# BatteryChargerSwitch.net
KiCad netlist of a schematic drawn in Altium Designer
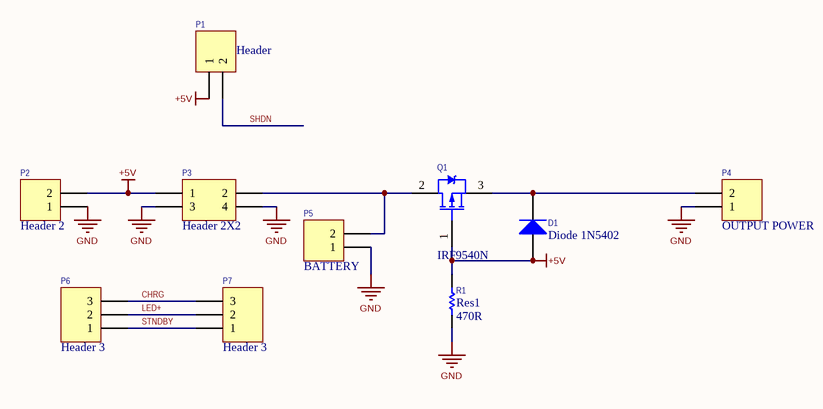
[diagram p0: BatteryChargerSwitch.SchDoc]

(export (version "E")
  (design (tool "Eeschema 10.0.6"))
  (components
    (comp (ref "D1")
      (value "Diode 1N5402")
      (footprint "1N5408 DO-201AD")
      (description "3 Amp General Purpose Rectifier")
      (fields (field (name "PUBLISHER") "Altium Limited"))
      (libsource (lib "Miscellaneous Devices") (part "Diode 1N5402"))
    )
    (comp (ref "P1")
      (value "Header")
      (footprint "KF301 2PIN")
      (description "Header, 2-Pin")
      (fields (field (name "PUBLISHER") "Altium Limited"))
      (libsource (lib "") (part "Header 2_1"))
    )
    (comp (ref "P2")
      (value "Header 2")
      (footprint "KF301 2PIN")
      (description "Header, 2-Pin")
      (fields (field (name "PUBLISHER") "Altium Limited"))
      (libsource (lib "Miscellaneous Connectors") (part "Header 2"))
    )
    (comp (ref "P3")
      (value "Header 2X2")
      (footprint "TP5100_MODULE")
      (description "Header, 2-Pin, Dual row")
      (fields (field (name "PUBLISHER") "Altium Limited"))
      (libsource (lib "Miscellaneous Connectors") (part "Header 2X2"))
    )
    (comp (ref "P4")
      (value "OUTPUT POWER")
      (footprint "KF301 2PIN")
      (description "Header, 2-Pin")
      (fields (field (name "PUBLISHER") "Altium Limited"))
      (libsource (lib "") (part "Header 2_1"))
    )
    (comp (ref "P5")
      (value "BATTERY")
      (footprint "KF301 2PIN")
      (description "Header, 2-Pin")
      (fields (field (name "PUBLISHER") "Altium Limited"))
      (libsource (lib "Miscellaneous Connectors") (part "Header 2"))
    )
    (comp (ref "P6")
      (value "Header 3")
      (footprint "HDR1X3")
      (description "Header, 3-Pin")
      (fields (field (name "PUBLISHER") "Altium Limited"))
      (libsource (lib "Miscellaneous Connectors") (part "Header 3"))
    )
    (comp (ref "P7")
      (value "Header 3")
      (footprint "HDR1X3")
      (description "Header, 3-Pin")
      (fields (field (name "PUBLISHER") "Altium Limited"))
      (libsource (lib "") (part "Header 3_1"))
    )
    (comp (ref "Q1")
      (value "IRF9540N")
      (footprint "TO-220 AB")
      (description "HEXFET Power MOSFET")
      (fields (field (name "PUBLISHER") "Altium Limited"))
      (libsource (lib "IR Discrete MOSFET - Power") (part "IRF9540N"))
    )
    (comp (ref "R1")
      (value "Res1")
      (footprint "Axial 0_25 W, 0_4 IN LEAD PITCH")
      (description "Resistor")
      (fields (field (name "ALTIUM_VALUE") "470R") (field (name "PUBLISHER") "Altium Limited"))
      (libsource (lib "Miscellaneous Devices") (part "Res1"))
    )
  )
  (nets
    (net (code "1") (name "+5V") (class "Default")
      (node (ref "D1") (pin "1") (pinfunction "A_1") (pintype "passive"))
      (node (ref "P1") (pin "1") (pinfunction "1_1") (pintype "passive"))
      (node (ref "P2") (pin "2") (pinfunction "2_2") (pintype "passive"))
      (node (ref "P3") (pin "1") (pinfunction "1_1") (pintype "passive"))
      (node (ref "Q1") (pin "1") (pinfunction "G_1") (pintype "passive"))
      (node (ref "R1") (pin "2") (pinfunction "2_2") (pintype "passive"))
    )
    (net (code "2") (name "/CHRG") (class "Default")
      (node (ref "P6") (pin "3") (pinfunction "3_3") (pintype "passive"))
      (node (ref "P7") (pin "3") (pinfunction "3_3") (pintype "passive"))
    )
    (net (code "3") (name "/LED+") (class "Default")
      (node (ref "P6") (pin "2") (pinfunction "2_2") (pintype "passive"))
      (node (ref "P7") (pin "2") (pinfunction "2_2") (pintype "passive"))
    )
    (net (code "4") (name "/SHDN") (class "Default")
      (node (ref "P1") (pin "2") (pinfunction "2_2") (pintype "passive"))
    )
    (net (code "5") (name "/STNDBY") (class "Default")
      (node (ref "P6") (pin "1") (pinfunction "1_1") (pintype "passive"))
      (node (ref "P7") (pin "1") (pinfunction "1_1") (pintype "passive"))
    )
    (net (code "6") (name "GND") (class "Default")
      (node (ref "P2") (pin "1") (pinfunction "1_1") (pintype "passive"))
      (node (ref "P3") (pin "3") (pinfunction "3_3") (pintype "passive"))
      (node (ref "P3") (pin "4") (pinfunction "4_4") (pintype "passive"))
      (node (ref "P4") (pin "1") (pinfunction "1_1") (pintype "passive"))
      (node (ref "P5") (pin "1") (pinfunction "1_1") (pintype "passive"))
      (node (ref "R1") (pin "1") (pinfunction "1_1") (pintype "passive"))
    )
    (net (code "7") (name "Net-(D1-K)") (class "Default")
      (node (ref "D1") (pin "2") (pinfunction "K_2") (pintype "passive"))
      (node (ref "P4") (pin "2") (pinfunction "2_2") (pintype "passive"))
      (node (ref "Q1") (pin "3") (pinfunction "S_3") (pintype "passive"))
    )
    (net (code "8") (name "Net-(Q1-D)") (class "Default")
      (node (ref "P3") (pin "2") (pinfunction "2_2") (pintype "passive"))
      (node (ref "P5") (pin "2") (pinfunction "2_2") (pintype "passive"))
      (node (ref "Q1") (pin "2") (pinfunction "D_2") (pintype "passive"))
    )
  )
)
